# 9_-MODEM_POWER.net
KiCad netlist of a schematic drawn in Altium Designer
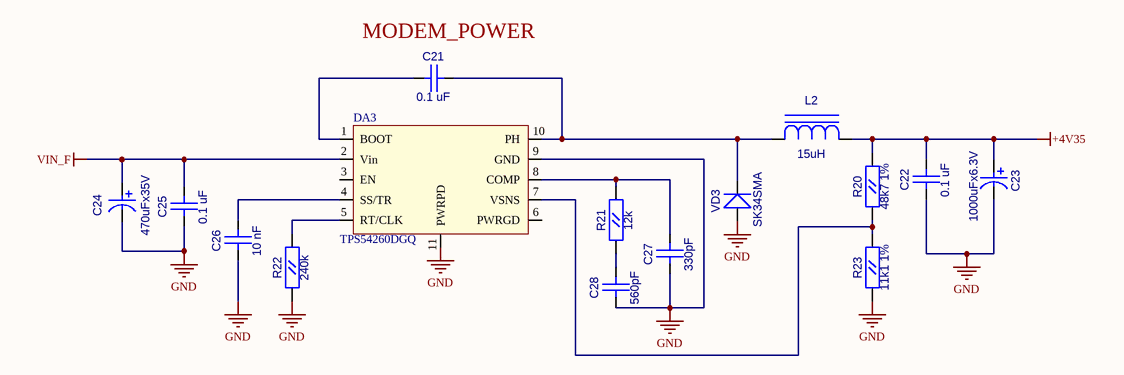
[diagram p0: [9]-MODEM_POWER.SchDoc]

(export (version "E")
  (design (tool "Eeschema 10.0.6"))
  (components
    (comp (ref "C21")
      (value "0.1 uF")
      (footprint "CC0603")
      (description "CC0603")
      (libsource (lib "gprs_modem_2") (part "CC0603"))
    )
    (comp (ref "C22")
      (value "0.1 uF")
      (footprint "CC0603")
      (description "CC0603")
      (libsource (lib "gprs_modem_2") (part "CC0603"))
    )
    (comp (ref "C23")
      (value "1000uFx6.3V")
      (footprint "CC8X3.5")
      (description "CAP0.35")
      (libsource (lib "gprs_modem_2") (part "CAP0.35"))
    )
    (comp (ref "C24")
      (value "470uFx35V")
      (footprint "CC16X10_CAP0.5(1)(Primary)")
      (description "CAP0.5(1)")
      (libsource (lib "gprs_modem_2") (part "CAP0.5(1)"))
    )
    (comp (ref "C25")
      (value "0.1 uF")
      (footprint "CC0603")
      (description "CC0603")
      (libsource (lib "gprs_modem_2") (part "CC0603"))
    )
    (comp (ref "C26")
      (value "10 nF")
      (footprint "CC0603")
      (description "CC0603")
      (libsource (lib "gprs_modem_2") (part "CC0603"))
    )
    (comp (ref "C27")
      (value "330pF")
      (footprint "CC0603")
      (description "CC0603")
      (libsource (lib "gprs_modem_2") (part "CC0603"))
    )
    (comp (ref "C28")
      (value "560pF")
      (footprint "CC0603")
      (description "CC0603")
      (libsource (lib "gprs_modem_2") (part "CC0603"))
    )
    (comp (ref "DA3")
      (value "TPS54260DGQ")
      (footprint "S-PDSO-G10")
      (libsource (lib "gprs_modem_2") (part "TPS54260DGQ"))
    )
    (comp (ref "L2")
      (value "15uH")
      (footprint "SDR0805")
      (description "SDR0805")
      (libsource (lib "gprs_modem_2") (part "SDR0805"))
    )
    (comp (ref "R20")
      (value "48k7 1%")
      (footprint "RC0603")
      (description "RC0603")
      (libsource (lib "gprs_modem_2") (part "RC0603"))
    )
    (comp (ref "R21")
      (value "12k")
      (footprint "RC0603")
      (description "RC0603")
      (libsource (lib "gprs_modem_2") (part "RC0603"))
    )
    (comp (ref "R22")
      (value "240k")
      (footprint "RC0603")
      (description "RC0603")
      (libsource (lib "gprs_modem_2") (part "RC0603"))
    )
    (comp (ref "R23")
      (value "11k1 1%")
      (footprint "RC0603")
      (description "RC0603")
      (libsource (lib "gprs_modem_2") (part "RC0603"))
    )
    (comp (ref "VD3")
      (value "SK34SMA")
      (footprint "SMA")
      (description "Schottky Rectifier")
      (libsource (lib "gprs_modem") (part "SK34SMA"))
    )
  )
  (nets
    (net (code "1") (name "+4V35") (class "Default")
      (node (ref "C22") (pin "1") (pinfunction "A_1") (pintype "passive"))
      (node (ref "C23") (pin "1") (pintype "passive"))
      (node (ref "L2") (pin "2") (pinfunction "A_2") (pintype "passive"))
      (node (ref "R20") (pin "2") (pinfunction "B_2") (pintype "passive"))
    )
    (net (code "2") (name "GND") (class "Default")
      (node (ref "C22") (pin "2") (pinfunction "B_2") (pintype "passive"))
      (node (ref "C23") (pin "2") (pintype "passive"))
      (node (ref "C24") (pin "1") (pintype "passive"))
      (node (ref "C25") (pin "2") (pinfunction "B_2") (pintype "passive"))
      (node (ref "C26") (pin "2") (pinfunction "B_2") (pintype "passive"))
      (node (ref "C27") (pin "2") (pinfunction "B_2") (pintype "passive"))
      (node (ref "C28") (pin "2") (pinfunction "B_2") (pintype "passive"))
      (node (ref "DA3") (pin "11") (pinfunction "PWRPD_11") (pintype "passive"))
      (node (ref "DA3") (pin "9") (pinfunction "GND_9") (pintype "passive"))
      (node (ref "R22") (pin "1") (pinfunction "A_1") (pintype "passive"))
      (node (ref "R23") (pin "1") (pinfunction "A_1") (pintype "passive"))
      (node (ref "VD3") (pin "1") (pinfunction "A_1") (pintype "passive"))
    )
    (net (code "3") (name "Net-(C21-A)") (class "Default")
      (node (ref "C21") (pin "1") (pinfunction "A_1") (pintype "passive"))
      (node (ref "DA3") (pin "10") (pinfunction "PH_10") (pintype "passive"))
      (node (ref "L2") (pin "1") (pinfunction "C_1") (pintype "passive"))
      (node (ref "VD3") (pin "2") (pinfunction "K_2") (pintype "passive"))
    )
    (net (code "4") (name "Net-(C21-B)") (class "Default")
      (node (ref "C21") (pin "2") (pinfunction "B_2") (pintype "passive"))
      (node (ref "DA3") (pin "1") (pinfunction "BOOT_1") (pintype "passive"))
    )
    (net (code "5") (name "Net-(C26-A)") (class "Default")
      (node (ref "C26") (pin "1") (pinfunction "A_1") (pintype "passive"))
      (node (ref "DA3") (pin "4") (pinfunction "SS/TR_4") (pintype "passive"))
    )
    (net (code "6") (name "Net-(C27-A)") (class "Default")
      (node (ref "C27") (pin "1") (pinfunction "A_1") (pintype "passive"))
      (node (ref "DA3") (pin "8") (pinfunction "COMP_8") (pintype "passive"))
      (node (ref "R21") (pin "2") (pinfunction "B_2") (pintype "passive"))
    )
    (net (code "7") (name "Net-(C28-A)") (class "Default")
      (node (ref "C28") (pin "1") (pinfunction "A_1") (pintype "passive"))
      (node (ref "R21") (pin "1") (pinfunction "A_1") (pintype "passive"))
    )
    (net (code "8") (name "Net-(DA3-RT{slash}CLK)") (class "Default")
      (node (ref "DA3") (pin "5") (pinfunction "RT/CLK_5") (pintype "passive"))
      (node (ref "R22") (pin "2") (pinfunction "B_2") (pintype "passive"))
    )
    (net (code "9") (name "Net-(DA3-VSNS)") (class "Default")
      (node (ref "DA3") (pin "7") (pinfunction "VSNS_7") (pintype "passive"))
      (node (ref "R20") (pin "1") (pinfunction "A_1") (pintype "passive"))
      (node (ref "R23") (pin "2") (pinfunction "B_2") (pintype "passive"))
    )
    (net (code "10") (name "VIN_F") (class "Default")
      (node (ref "C24") (pin "2") (pintype "passive"))
      (node (ref "C25") (pin "1") (pinfunction "A_1") (pintype "passive"))
      (node (ref "DA3") (pin "2") (pinfunction "Vin_2") (pintype "passive"))
    )
    (net (code "11") (name "unconnected-(DA3-EN-Pad3)") (class "Default")
      (node (ref "DA3") (pin "3") (pinfunction "EN_3") (pintype "passive"))
    )
    (net (code "12") (name "unconnected-(DA3-PWRGD-Pad6)") (class "Default")
      (node (ref "DA3") (pin "6") (pinfunction "PWRGD_6") (pintype "passive"))
    )
  )
)
